# lcd_new.net
KiCad netlist of a schematic drawn in EAGLE
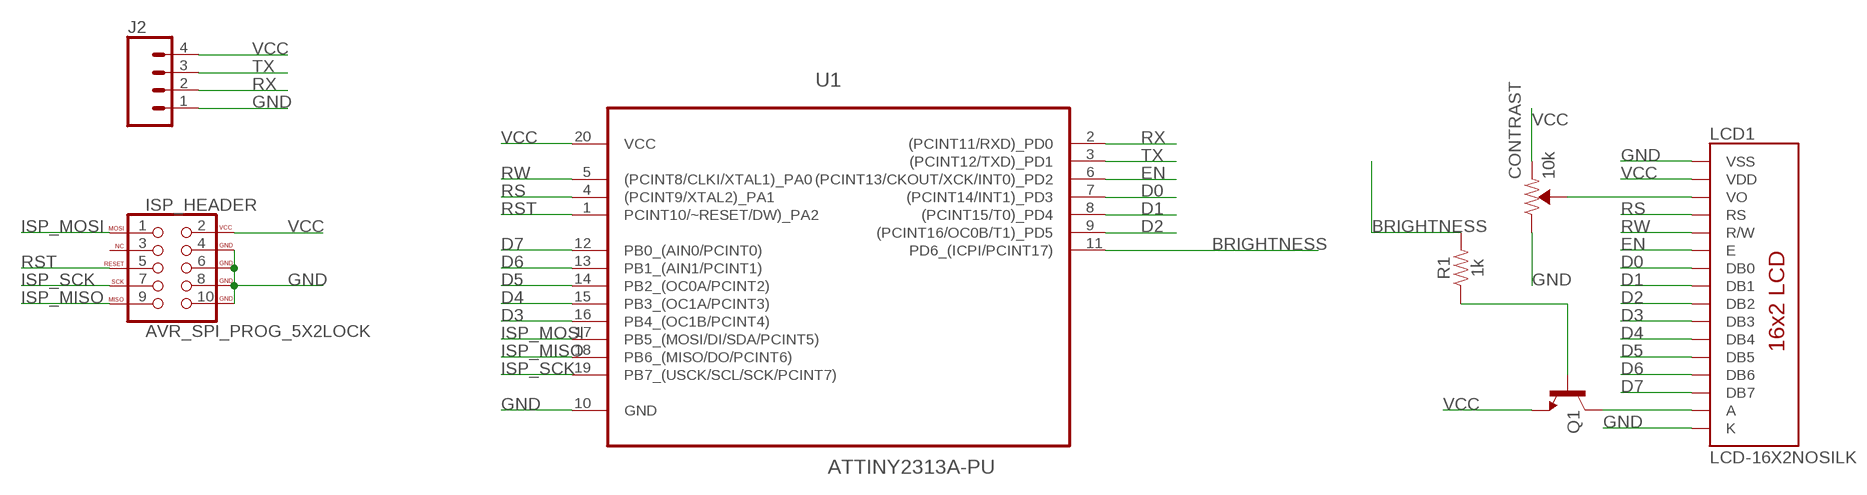
[diagram p0: schematic, sheet 1]

(export (version "E")
  (design (tool "Eeschema 10.0.6"))
  (components
    (comp (ref "CONTRAST")
      (value "10k")
      (footprint "eagle-import:TRIMPOT-SMD-5MM")
      (libsource (lib "eagle-import") (part "TRIMPOT-SMD-5MM-CLOSED-1/4W-20%"))
    )
    (comp (ref "ISP_HEADER")
      (value "AVR_SPI_PROG_5X2LOCK")
      (footprint "eagle-import:2X5-SHROUDED_LOCK")
      (libsource (lib "eagle-import") (part "AVR_SPI_PROG_5X2LOCK"))
    )
    (comp (ref "J2")
      (value "CONN_04")
      (footprint "eagle-import:1X04")
      (libsource (lib "eagle-import") (part "CONN_04"))
    )
    (comp (ref "LCD1")
      (value "LCD-16X2NOSILK")
      (footprint "eagle-import:LCD-16X2_NOSILK")
      (libsource (lib "eagle-import") (part "LCD-16X2NOSILK"))
    )
    (comp (ref "Q1")
      (value "TRANS_NPN-2N3904")
      (footprint "eagle-import:TO-92")
      (libsource (lib "eagle-import") (part "TRANS_NPN-2N3904"))
    )
    (comp (ref "R1")
      (value "1k")
      (footprint "eagle-import:AXIAL-0.3")
      (libsource (lib "eagle-import") (part "1KOHM-HORIZ-1/4W-5%"))
    )
    (comp (ref "U1")
      (value "ATTINY2313A-PU")
      (footprint "eagle-import:DIP254P762X533-20")
      (libsource (lib "eagle-import") (part "ATTINY2313A-PU"))
    )
  )
  (nets
    (net (code "1") (name "/BRIGHTNESS") (class "Default")
      (node (ref "R1") (pin "P$2") (pinfunction "2_P$2") (pintype "passive"))
      (node (ref "U1") (pin "11") (pinfunction "PD6_(ICPI/PCINT17)_11") (pintype "bidirectional"))
    )
    (net (code "2") (name "/D0") (class "Default")
      (node (ref "LCD1") (pin "7") (pinfunction "DB0_7") (pintype "bidirectional"))
      (node (ref "U1") (pin "7") (pinfunction "(PCINT14/INT1)_PD3_7") (pintype "bidirectional"))
    )
    (net (code "3") (name "/D1") (class "Default")
      (node (ref "LCD1") (pin "8") (pinfunction "DB1_8") (pintype "bidirectional"))
      (node (ref "U1") (pin "8") (pinfunction "(PCINT15/T0)_PD4_8") (pintype "bidirectional"))
    )
    (net (code "4") (name "/D2") (class "Default")
      (node (ref "LCD1") (pin "9") (pinfunction "DB2_9") (pintype "bidirectional"))
      (node (ref "U1") (pin "9") (pinfunction "(PCINT16/OC0B/T1)_PD5_9") (pintype "bidirectional"))
    )
    (net (code "5") (name "/D3") (class "Default")
      (node (ref "LCD1") (pin "10") (pinfunction "DB3_10") (pintype "bidirectional"))
      (node (ref "U1") (pin "16") (pinfunction "PB4_(OC1B/PCINT4)_16") (pintype "bidirectional"))
    )
    (net (code "6") (name "/D4") (class "Default")
      (node (ref "LCD1") (pin "11") (pinfunction "DB4_11") (pintype "bidirectional"))
      (node (ref "U1") (pin "15") (pinfunction "PB3_(OC1A/PCINT3)_15") (pintype "bidirectional"))
    )
    (net (code "7") (name "/D5") (class "Default")
      (node (ref "LCD1") (pin "12") (pinfunction "DB5_12") (pintype "bidirectional"))
      (node (ref "U1") (pin "14") (pinfunction "PB2_(OC0A/PCINT2)_14") (pintype "bidirectional"))
    )
    (net (code "8") (name "/D6") (class "Default")
      (node (ref "LCD1") (pin "13") (pinfunction "DB6_13") (pintype "bidirectional"))
      (node (ref "U1") (pin "13") (pinfunction "PB1_(AIN1/PCINT1)_13") (pintype "bidirectional"))
    )
    (net (code "9") (name "/D7") (class "Default")
      (node (ref "LCD1") (pin "14") (pinfunction "DB7_14") (pintype "bidirectional"))
      (node (ref "U1") (pin "12") (pinfunction "PB0_(AIN0/PCINT0)_12") (pintype "bidirectional"))
    )
    (net (code "10") (name "/EN") (class "Default")
      (node (ref "LCD1") (pin "6") (pinfunction "E_6") (pintype "input"))
      (node (ref "U1") (pin "6") (pinfunction "(PCINT13/CKOUT/XCK/INT0)_PD2_6") (pintype "bidirectional"))
    )
    (net (code "11") (name "/GND") (class "Default")
      (node (ref "CONTRAST") (pin "C") (pinfunction "CW_C") (pintype "passive"))
      (node (ref "ISP_HEADER") (pin "10") (pinfunction "GND_10") (pintype "power_in"))
      (node (ref "ISP_HEADER") (pin "4") (pinfunction "GND_4") (pintype "power_in"))
      (node (ref "ISP_HEADER") (pin "6") (pinfunction "GND_6") (pintype "power_in"))
      (node (ref "ISP_HEADER") (pin "8") (pinfunction "GND_8") (pintype "power_in"))
      (node (ref "J2") (pin "1") (pinfunction "1_1") (pintype "passive"))
      (node (ref "LCD1") (pin "1") (pinfunction "VSS_1") (pintype "power_in"))
      (node (ref "LCD1") (pin "16") (pinfunction "K_16") (pintype "power_in"))
      (node (ref "U1") (pin "10") (pinfunction "GND_10") (pintype "passive"))
    )
    (net (code "12") (name "/ISP_MISO") (class "Default")
      (node (ref "ISP_HEADER") (pin "9") (pinfunction "MISO_9") (pintype "passive"))
      (node (ref "U1") (pin "18") (pinfunction "PB6_(MISO/DO/PCINT6)_18") (pintype "bidirectional"))
    )
    (net (code "13") (name "/ISP_MOSI") (class "Default")
      (node (ref "ISP_HEADER") (pin "1") (pinfunction "MOSI_1") (pintype "passive"))
      (node (ref "U1") (pin "17") (pinfunction "PB5_(MOSI/DI/SDA/PCINT5)_17") (pintype "bidirectional"))
    )
    (net (code "14") (name "/ISP_SCK") (class "Default")
      (node (ref "ISP_HEADER") (pin "7") (pinfunction "SCK_7") (pintype "passive"))
      (node (ref "U1") (pin "19") (pinfunction "PB7_(USCK/SCL/SCK/PCINT7)_19") (pintype "bidirectional"))
    )
    (net (code "15") (name "/RS") (class "Default")
      (node (ref "LCD1") (pin "4") (pinfunction "RS_4") (pintype "input"))
      (node (ref "U1") (pin "4") (pinfunction "(PCINT9/XTAL2)_PA1_4") (pintype "bidirectional"))
    )
    (net (code "16") (name "/RST") (class "Default")
      (node (ref "ISP_HEADER") (pin "5") (pinfunction "RESET_5") (pintype "passive"))
      (node (ref "U1") (pin "1") (pinfunction "PCINT10/~{RESET/DW})_PA2_1") (pintype "bidirectional"))
    )
    (net (code "17") (name "/RW") (class "Default")
      (node (ref "LCD1") (pin "5") (pinfunction "R/W_5") (pintype "input"))
      (node (ref "U1") (pin "5") (pinfunction "(PCINT8/CLKI/XTAL1)_PA0_5") (pintype "bidirectional"))
    )
    (net (code "18") (name "/RX") (class "Default")
      (node (ref "J2") (pin "2") (pinfunction "2_2") (pintype "passive"))
      (node (ref "U1") (pin "2") (pinfunction "(PCINT11/RXD)_PD0_2") (pintype "bidirectional"))
    )
    (net (code "19") (name "/TX") (class "Default")
      (node (ref "J2") (pin "3") (pinfunction "3_3") (pintype "passive"))
      (node (ref "U1") (pin "3") (pinfunction "(PCINT12/TXD)_PD1_3") (pintype "bidirectional"))
    )
    (net (code "20") (name "/VCC") (class "Default")
      (node (ref "CONTRAST") (pin "A") (pinfunction "CCW_A") (pintype "passive"))
      (node (ref "ISP_HEADER") (pin "2") (pinfunction "VCC_2") (pintype "power_in"))
      (node (ref "J2") (pin "4") (pinfunction "4_4") (pintype "passive"))
      (node (ref "LCD1") (pin "2") (pinfunction "VDD_2") (pintype "power_in"))
      (node (ref "Q1") (pin "1") (pinfunction "E_1") (pintype "passive"))
      (node (ref "U1") (pin "20") (pinfunction "VCC_20") (pintype "power_in"))
    )
    (net (code "21") (name "Net-(CONTRAST-WIPER)") (class "Default")
      (node (ref "CONTRAST") (pin "B") (pinfunction "WIPER_B") (pintype "passive"))
      (node (ref "LCD1") (pin "3") (pinfunction "VO_3") (pintype "bidirectional"))
    )
    (net (code "22") (name "Net-(LCD1-A)") (class "Default")
      (node (ref "LCD1") (pin "15") (pinfunction "A_15") (pintype "power_in"))
      (node (ref "Q1") (pin "3") (pinfunction "C_3") (pintype "passive"))
    )
    (net (code "23") (name "Net-(Q1-B)") (class "Default")
      (node (ref "Q1") (pin "2") (pinfunction "B_2") (pintype "passive"))
      (node (ref "R1") (pin "P$1") (pinfunction "1_P$1") (pintype "passive"))
    )
    (net (code "24") (name "unconnected-(ISP_HEADER-NC-Pad3)") (class "Default")
      (node (ref "ISP_HEADER") (pin "3") (pinfunction "NC_3") (pintype "no_connect"))
    )
  )
)
